# plugV17-Add-Large-Cap-to-support-RELAY-s.net
KiCad netlist of a schematic drawn in EAGLE
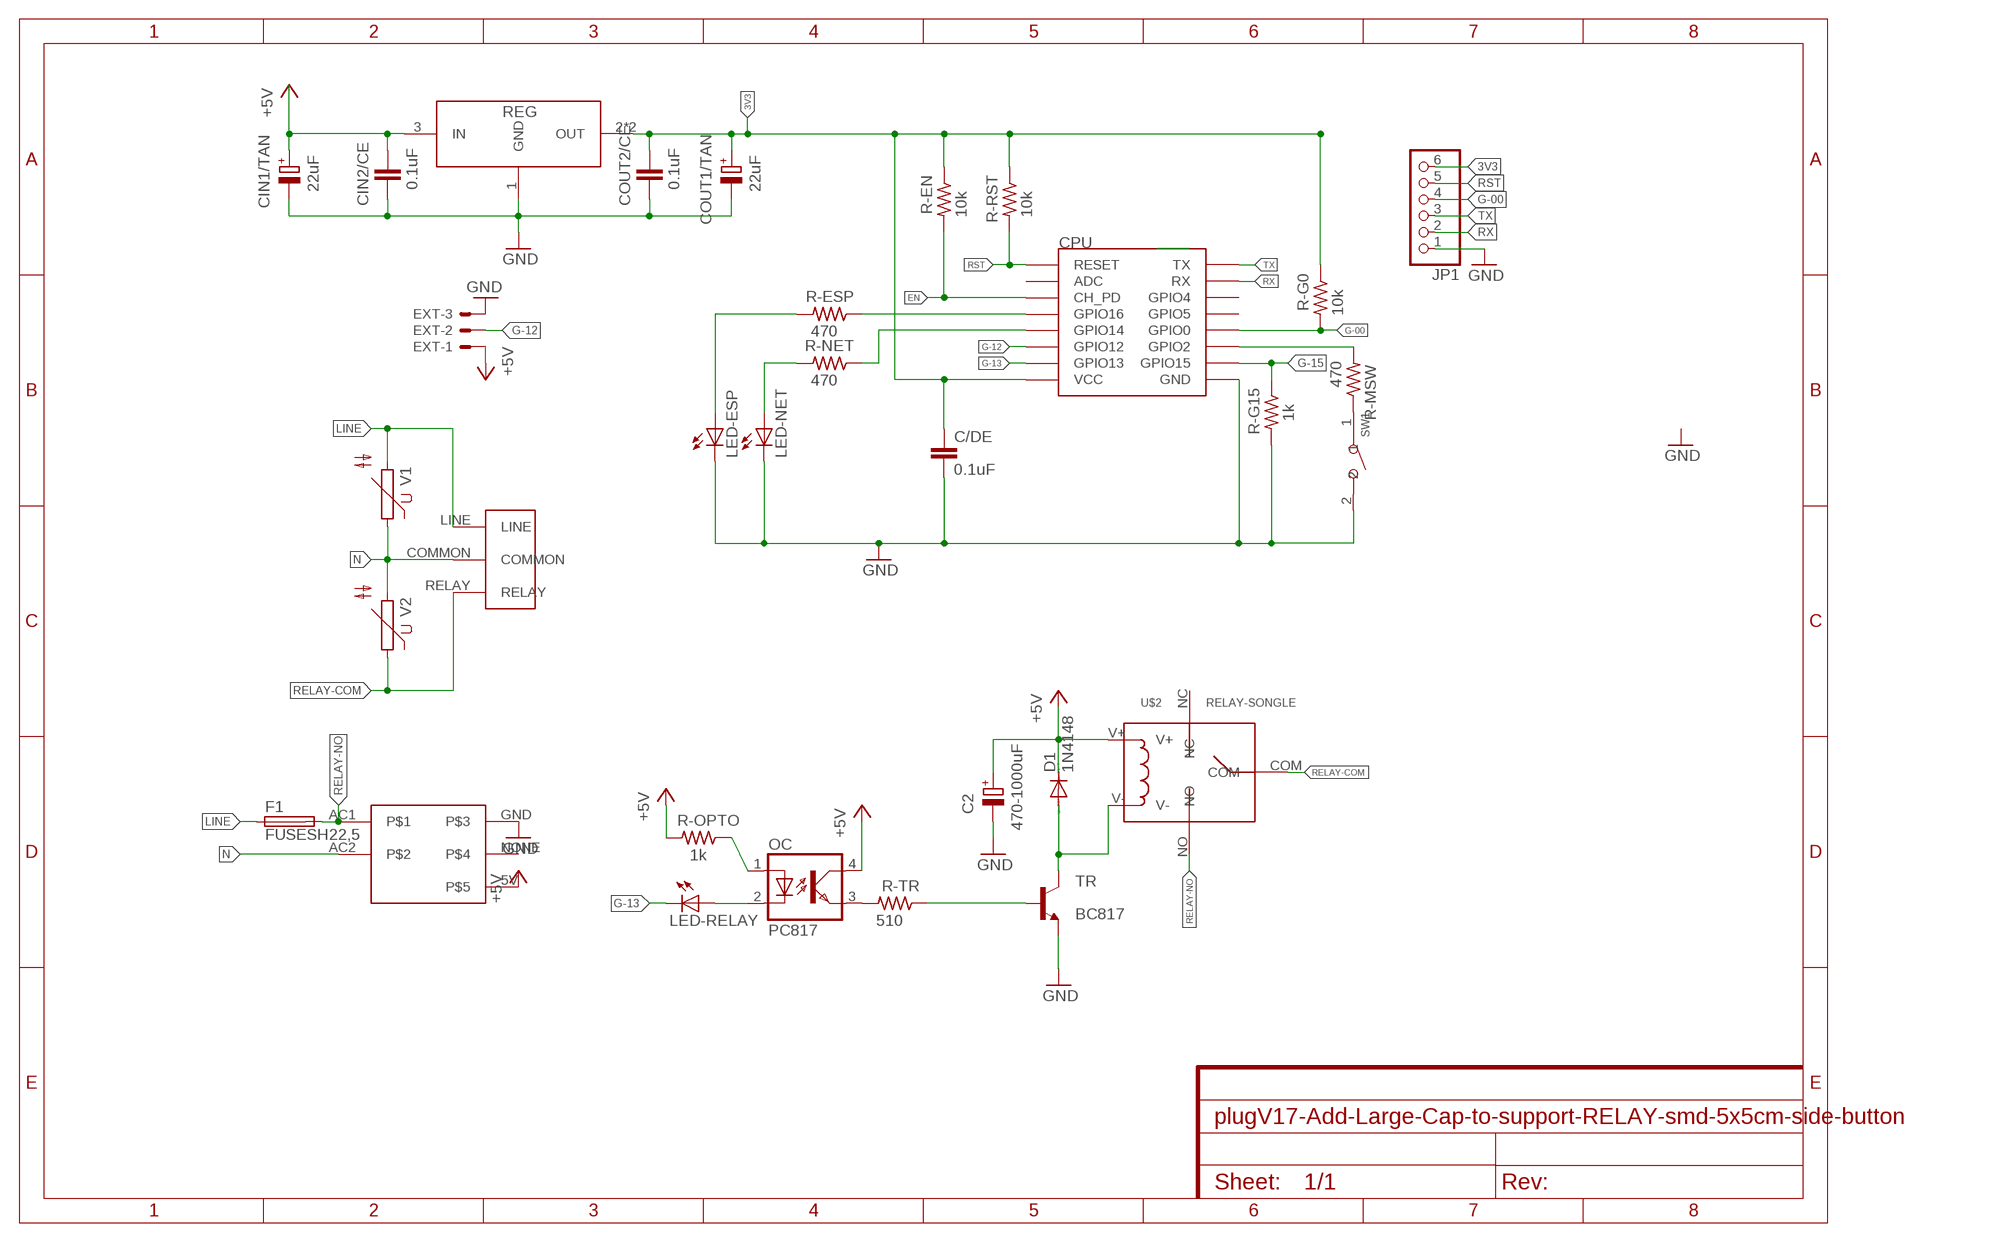
[diagram p0: schematic, sheet 1]

(export (version "E")
  (design (tool "Eeschema 10.0.6"))
  (components
    (comp (ref "C/DE")
      (value "0.1uF")
      (footprint "eagle-import:C0805")
      (libsource (lib "eagle-import") (part "C-EUC0805"))
    )
    (comp (ref "C2")
      (value "470-1000uF")
      (footprint "eagle-import:E3,5-8")
      (libsource (lib "eagle-import") (part "CPOL-EUE3.5-8"))
    )
    (comp (ref "CIN1/TAN")
      (value "22uF")
      (footprint "eagle-import:B_3528-21R")
      (libsource (lib "eagle-import") (part "CPOL-EUB/3528-21R"))
    )
    (comp (ref "CIN2/CE")
      (value "0.1uF")
      (footprint "eagle-import:C0805K")
      (libsource (lib "eagle-import") (part "C-EUC0805K"))
    )
    (comp (ref "COUT1/TAN")
      (value "22uF")
      (footprint "eagle-import:B_3528-21R")
      (libsource (lib "eagle-import") (part "CPOL-EUB/3528-21R"))
    )
    (comp (ref "COUT2/CE")
      (value "0.1uF")
      (footprint "eagle-import:C0805K")
      (libsource (lib "eagle-import") (part "C-EUC0805K"))
    )
    (comp (ref "CPU")
      (value "ESP12SMD")
      (footprint "eagle-import:ESP12-SMD")
      (libsource (lib "eagle-import") (part "ESP12SMD"))
    )
    (comp (ref "D1")
      (value "1N4148")
      (footprint "eagle-import:DO35-7")
      (libsource (lib "eagle-import") (part "1N4148DO35-7"))
    )
    (comp (ref "EXT")
      (value "53048-03")
      (footprint "eagle-import:53048-03")
      (fields (field (name "MF") "WALDOM/MOLEX") (field (name "MPN") "53048-0310"))
      (libsource (lib "eagle-import") (part "53?-03048"))
    )
    (comp (ref "F1")
      (value "FUSESH22,5")
      (footprint "eagle-import:SH22,5")
      (libsource (lib "eagle-import") (part "FUSESH22,5"))
    )
    (comp (ref "JP1")
      (value "PINHD-1X6")
      (footprint "eagle-import:1X06")
      (libsource (lib "eagle-import") (part "PINHD-1X6"))
    )
    (comp (ref "LED-ESP")
      (value "LEDCHIPLED_0805")
      (footprint "eagle-import:CHIPLED_0805")
      (libsource (lib "eagle-import") (part "LEDCHIPLED_0805"))
    )
    (comp (ref "LED-NET")
      (value "LEDCHIPLED_0805")
      (footprint "eagle-import:CHIPLED_0805")
      (libsource (lib "eagle-import") (part "LEDCHIPLED_0805"))
    )
    (comp (ref "LED-RELAY")
      (value "LEDCHIPLED_0805")
      (footprint "eagle-import:CHIPLED_0805")
      (libsource (lib "eagle-import") (part "LEDCHIPLED_0805"))
    )
    (comp (ref "OC")
      (value "PC817")
      (footprint "eagle-import:DIL04")
      (fields (field (name "MPN") "PC817X4J000F"))
      (libsource (lib "eagle-import") (part "PC817"))
    )
    (comp (ref "R-EN")
      (value "10k")
      (footprint "eagle-import:M0805")
      (libsource (lib "eagle-import") (part "R-US_M0805"))
    )
    (comp (ref "R-ESP")
      (value "470")
      (footprint "eagle-import:M0805")
      (libsource (lib "eagle-import") (part "R-US_M0805"))
    )
    (comp (ref "R-G0")
      (value "10k")
      (footprint "eagle-import:M0805")
      (libsource (lib "eagle-import") (part "R-US_M0805"))
    )
    (comp (ref "R-G15")
      (value "1k")
      (footprint "eagle-import:M0805")
      (libsource (lib "eagle-import") (part "R-US_M0805"))
    )
    (comp (ref "R-MSW")
      (value "470")
      (footprint "eagle-import:M0805")
      (libsource (lib "eagle-import") (part "R-US_M0805"))
    )
    (comp (ref "R-NET")
      (value "470")
      (footprint "eagle-import:M0805")
      (libsource (lib "eagle-import") (part "R-US_M0805"))
    )
    (comp (ref "R-OPTO")
      (value "1k")
      (footprint "eagle-import:M0805")
      (libsource (lib "eagle-import") (part "R-US_M0805"))
    )
    (comp (ref "R-RST")
      (value "10k")
      (footprint "eagle-import:M0805")
      (libsource (lib "eagle-import") (part "R-US_M0805"))
    )
    (comp (ref "R-TR")
      (value "510")
      (footprint "eagle-import:M0805")
      (libsource (lib "eagle-import") (part "R-US_M0805"))
    )
    (comp (ref "REG")
      (value "AMS1117-3.3")
      (footprint "eagle-import:SOT-223")
      (libsource (lib "eagle-import") (part "AMS1117-3.3"))
    )
    (comp (ref "SW1")
      (value "DIP-BUTTON(2P-6.0X3.0X4.3MM)-TS-1101F")
      (footprint "eagle-import:SW2-5.0-6.0X3.0X4.3MM")
      (libsource (lib "eagle-import") (part "DIP-BUTTON(2P-6.0X3.0X4.3MM)-TS-1101F"))
    )
    (comp (ref "TR")
      (value "BC817")
      (footprint "eagle-import:SOT23-BEC")
      (libsource (lib "eagle-import") (part "BC817SMD-16"))
    )
    (comp (ref "U$1")
      (value "POWER-RELAY-FOOTPRINT")
      (footprint "eagle-import:POWER-RELAY-FOOTPRINT")
      (libsource (lib "eagle-import") (part "POWER-RELAY-FOOTPRINT"))
    )
    (comp (ref "U$2")
      (value "RELAY-SONGLE")
      (footprint "eagle-import:RELAY-SONGLE")
      (libsource (lib "eagle-import") (part "RELAY-SONGLE"))
    )
    (comp (ref "U$4")
      (value "POWERSUPPLY-5V-700MA")
      (footprint "eagle-import:POWERSUPPLY-5V-700MA")
      (libsource (lib "eagle-import") (part "POWERSUPPLY-5V-700MA"))
    )
    (comp (ref "V1")
      (value "S14K11")
      (footprint "eagle-import:S14K11")
      (libsource (lib "eagle-import") (part "S14K11"))
    )
    (comp (ref "V2")
      (value "S14K11")
      (footprint "eagle-import:S14K11")
      (libsource (lib "eagle-import") (part "S14K11"))
    )
  )
  (nets
    (net (code "1") (name "+5V") (class "Default")
      (node (ref "C2") (pin "+") (pinfunction "+_+") (pintype "passive"))
      (node (ref "CIN1/TAN") (pin "+") (pinfunction "+_+") (pintype "passive"))
      (node (ref "CIN2/CE") (pin "1") (pinfunction "1_1") (pintype "passive"))
      (node (ref "D1") (pin "C") (pinfunction "C_C") (pintype "passive"))
      (node (ref "EXT") (pin "1") (pinfunction "S_1") (pintype "passive"))
      (node (ref "OC") (pin "4") (pinfunction "COL_4") (pintype "passive"))
      (node (ref "R-OPTO") (pin "2") (pinfunction "2_2") (pintype "passive"))
      (node (ref "REG") (pin "3") (pinfunction "IN_3") (pintype "input"))
      (node (ref "U$2") (pin "V+") (pinfunction "V+_V+") (pintype "bidirectional"))
      (node (ref "U$4") (pin "5V") (pinfunction "P$5_5V") (pintype "bidirectional"))
    )
    (net (code "2") (name "3V3") (class "Default")
      (node (ref "C/DE") (pin "1") (pinfunction "1_1") (pintype "passive"))
      (node (ref "COUT1/TAN") (pin "+") (pinfunction "+_+") (pintype "passive"))
      (node (ref "COUT2/CE") (pin "1") (pinfunction "1_1") (pintype "passive"))
      (node (ref "CPU") (pin "VCC") (pinfunction "VCC_VCC") (pintype "bidirectional"))
      (node (ref "JP1") (pin "6") (pinfunction "6_6") (pintype "passive"))
      (node (ref "R-EN") (pin "1") (pinfunction "1_1") (pintype "passive"))
      (node (ref "R-G0") (pin "1") (pinfunction "1_1") (pintype "passive"))
      (node (ref "R-RST") (pin "1") (pinfunction "1_1") (pintype "passive"))
      (node (ref "REG") (pin "2") (pinfunction "OUT_2") (pintype "output"))
      (node (ref "REG") (pin "4") (pinfunction "OUT_4") (pintype "output"))
    )
    (net (code "3") (name "EN") (class "Default")
      (node (ref "CPU") (pin "CH_PD") (pinfunction "CH_PD_CH_PD") (pintype "bidirectional"))
      (node (ref "R-EN") (pin "2") (pinfunction "2_2") (pintype "passive"))
    )
    (net (code "4") (name "G-00") (class "Default")
      (node (ref "CPU") (pin "GPIO0") (pinfunction "GPIO0_GPIO0") (pintype "bidirectional"))
      (node (ref "JP1") (pin "4") (pinfunction "4_4") (pintype "passive"))
      (node (ref "R-G0") (pin "2") (pinfunction "2_2") (pintype "passive"))
    )
    (net (code "5") (name "G-12") (class "Default")
      (node (ref "CPU") (pin "GPIO12") (pinfunction "GPIO12_GPIO12") (pintype "bidirectional"))
      (node (ref "EXT") (pin "2") (pinfunction "S_2") (pintype "passive"))
    )
    (net (code "6") (name "G-13") (class "Default")
      (node (ref "CPU") (pin "GPIO13") (pinfunction "GPIO13_GPIO13") (pintype "bidirectional"))
      (node (ref "LED-RELAY") (pin "C") (pinfunction "C_C") (pintype "passive"))
    )
    (net (code "7") (name "G-15") (class "Default")
      (node (ref "CPU") (pin "GPIO15") (pinfunction "GPIO15_GPIO15") (pintype "bidirectional"))
      (node (ref "R-G15") (pin "1") (pinfunction "1_1") (pintype "passive"))
    )
    (net (code "8") (name "GND") (class "Default")
      (node (ref "C/DE") (pin "2") (pinfunction "2_2") (pintype "passive"))
      (node (ref "C2") (pin "-") (pinfunction "-_-") (pintype "passive"))
      (node (ref "CIN1/TAN") (pin "-") (pinfunction "-_-") (pintype "passive"))
      (node (ref "CIN2/CE") (pin "2") (pinfunction "2_2") (pintype "passive"))
      (node (ref "COUT1/TAN") (pin "-") (pinfunction "-_-") (pintype "passive"))
      (node (ref "COUT2/CE") (pin "2") (pinfunction "2_2") (pintype "passive"))
      (node (ref "CPU") (pin "GND") (pinfunction "GND_GND") (pintype "bidirectional"))
      (node (ref "EXT") (pin "3") (pinfunction "S_3") (pintype "passive"))
      (node (ref "JP1") (pin "1") (pinfunction "1_1") (pintype "passive"))
      (node (ref "LED-ESP") (pin "C") (pinfunction "C_C") (pintype "passive"))
      (node (ref "LED-NET") (pin "C") (pinfunction "C_C") (pintype "passive"))
      (node (ref "R-G15") (pin "2") (pinfunction "2_2") (pintype "passive"))
      (node (ref "REG") (pin "1") (pinfunction "GND_1") (pintype "passive"))
      (node (ref "SW1") (pin "2") (pinfunction "2_2") (pintype "bidirectional"))
      (node (ref "TR") (pin "E") (pinfunction "E_E") (pintype "passive"))
      (node (ref "U$4") (pin "GND") (pinfunction "P$3_GND") (pintype "bidirectional"))
    )
    (net (code "9") (name "LINE") (class "Default")
      (node (ref "F1") (pin "1") (pinfunction "1_1") (pintype "passive"))
      (node (ref "U$1") (pin "LINE") (pinfunction "LINE_LINE") (pintype "bidirectional"))
      (node (ref "V1") (pin "2") (pinfunction "2_2") (pintype "passive"))
    )
    (net (code "10") (name "N") (class "Default")
      (node (ref "U$1") (pin "COMMON") (pinfunction "COMMON_COMMON") (pintype "bidirectional"))
      (node (ref "U$4") (pin "AC2") (pinfunction "P$2_AC2") (pintype "bidirectional"))
      (node (ref "V1") (pin "1") (pinfunction "1_1") (pintype "passive"))
      (node (ref "V2") (pin "2") (pinfunction "2_2") (pintype "passive"))
    )
    (net (code "11") (name "Net-(CPU-PadGPIO2)") (class "Default")
      (node (ref "CPU") (pin "GPIO2") (pinfunction "GPIO2_GPIO2") (pintype "bidirectional"))
      (node (ref "R-MSW") (pin "2") (pinfunction "2_2") (pintype "passive"))
    )
    (net (code "12") (name "Net-(CPU-PadGPIO14)") (class "Default")
      (node (ref "CPU") (pin "GPIO14") (pinfunction "GPIO14_GPIO14") (pintype "bidirectional"))
      (node (ref "R-NET") (pin "1") (pinfunction "1_1") (pintype "passive"))
    )
    (net (code "13") (name "Net-(CPU-PadGPIO16)") (class "Default")
      (node (ref "CPU") (pin "GPIO16") (pinfunction "GPIO16_GPIO16") (pintype "bidirectional"))
      (node (ref "R-ESP") (pin "1") (pinfunction "1_1") (pintype "passive"))
    )
    (net (code "14") (name "Net-(D1-PadA)") (class "Default")
      (node (ref "D1") (pin "A") (pinfunction "A_A") (pintype "passive"))
      (node (ref "TR") (pin "C") (pinfunction "C_C") (pintype "passive"))
      (node (ref "U$2") (pin "V-") (pinfunction "V-_V-") (pintype "bidirectional"))
    )
    (net (code "15") (name "Net-(LED-ESP-PadA)") (class "Default")
      (node (ref "LED-ESP") (pin "A") (pinfunction "A_A") (pintype "passive"))
      (node (ref "R-ESP") (pin "2") (pinfunction "2_2") (pintype "passive"))
    )
    (net (code "16") (name "Net-(LED-NET-PadA)") (class "Default")
      (node (ref "LED-NET") (pin "A") (pinfunction "A_A") (pintype "passive"))
      (node (ref "R-NET") (pin "2") (pinfunction "2_2") (pintype "passive"))
    )
    (net (code "17") (name "Net-(OC-A)") (class "Default")
      (node (ref "OC") (pin "1") (pinfunction "A_1") (pintype "passive"))
      (node (ref "R-OPTO") (pin "1") (pinfunction "1_1") (pintype "passive"))
    )
    (net (code "18") (name "Net-(OC-C)") (class "Default")
      (node (ref "LED-RELAY") (pin "A") (pinfunction "A_A") (pintype "passive"))
      (node (ref "OC") (pin "2") (pinfunction "C_2") (pintype "passive"))
    )
    (net (code "19") (name "Net-(OC-EMIT)") (class "Default")
      (node (ref "OC") (pin "3") (pinfunction "EMIT_3") (pintype "passive"))
      (node (ref "R-TR") (pin "2") (pinfunction "2_2") (pintype "passive"))
    )
    (net (code "20") (name "Net-(R-MSW-Pad1)") (class "Default")
      (node (ref "R-MSW") (pin "1") (pinfunction "1_1") (pintype "passive"))
      (node (ref "SW1") (pin "1") (pinfunction "1_1") (pintype "bidirectional"))
    )
    (net (code "21") (name "Net-(R-TR-Pad1)") (class "Default")
      (node (ref "R-TR") (pin "1") (pinfunction "1_1") (pintype "passive"))
      (node (ref "TR") (pin "B") (pinfunction "B_B") (pintype "passive"))
    )
    (net (code "22") (name "RELAY-COM") (class "Default")
      (node (ref "U$1") (pin "RELAY") (pinfunction "RELAY_RELAY") (pintype "bidirectional"))
      (node (ref "U$2") (pin "COM") (pinfunction "COM_COM") (pintype "bidirectional"))
      (node (ref "V2") (pin "1") (pinfunction "1_1") (pintype "passive"))
    )
    (net (code "23") (name "RELAY-NO") (class "Default")
      (node (ref "F1") (pin "2") (pinfunction "2_2") (pintype "passive"))
      (node (ref "U$2") (pin "NO") (pinfunction "NO_NO") (pintype "bidirectional"))
      (node (ref "U$4") (pin "AC1") (pinfunction "P$1_AC1") (pintype "bidirectional"))
    )
    (net (code "24") (name "RST") (class "Default")
      (node (ref "CPU") (pin "RESET") (pinfunction "RESET_RESET") (pintype "bidirectional"))
      (node (ref "JP1") (pin "5") (pinfunction "5_5") (pintype "passive"))
      (node (ref "R-RST") (pin "2") (pinfunction "2_2") (pintype "passive"))
    )
    (net (code "25") (name "RX") (class "Default")
      (node (ref "CPU") (pin "RXD0") (pinfunction "RX_RXD0") (pintype "bidirectional"))
      (node (ref "JP1") (pin "2") (pinfunction "2_2") (pintype "passive"))
    )
    (net (code "26") (name "TX") (class "Default")
      (node (ref "CPU") (pin "TXD0") (pinfunction "TX_TXD0") (pintype "bidirectional"))
      (node (ref "JP1") (pin "3") (pinfunction "3_3") (pintype "passive"))
    )
    (net (code "27") (name "unconnected-(CPU-PadADC)") (class "Default")
      (node (ref "CPU") (pin "ADC") (pinfunction "ADC_ADC") (pintype "bidirectional"))
    )
    (net (code "28") (name "unconnected-(CPU-PadGPIO4)") (class "Default")
      (node (ref "CPU") (pin "GPIO4") (pinfunction "GPIO4_GPIO4") (pintype "bidirectional"))
    )
    (net (code "29") (name "unconnected-(CPU-PadGPIO5)") (class "Default")
      (node (ref "CPU") (pin "GPIO5") (pinfunction "GPIO5_GPIO5") (pintype "bidirectional"))
    )
    (net (code "30") (name "unconnected-(U$2-PadNC)") (class "Default")
      (node (ref "U$2") (pin "NC") (pinfunction "NC_NC") (pintype "bidirectional"))
    )
    (net (code "31") (name "unconnected-(U$4-P$4-PadNONE)") (class "Default")
      (node (ref "U$4") (pin "NONE") (pinfunction "P$4_NONE") (pintype "bidirectional"))
    )
  )
)
